# Sheet.net
KiCad netlist of a schematic drawn in Altium Designer
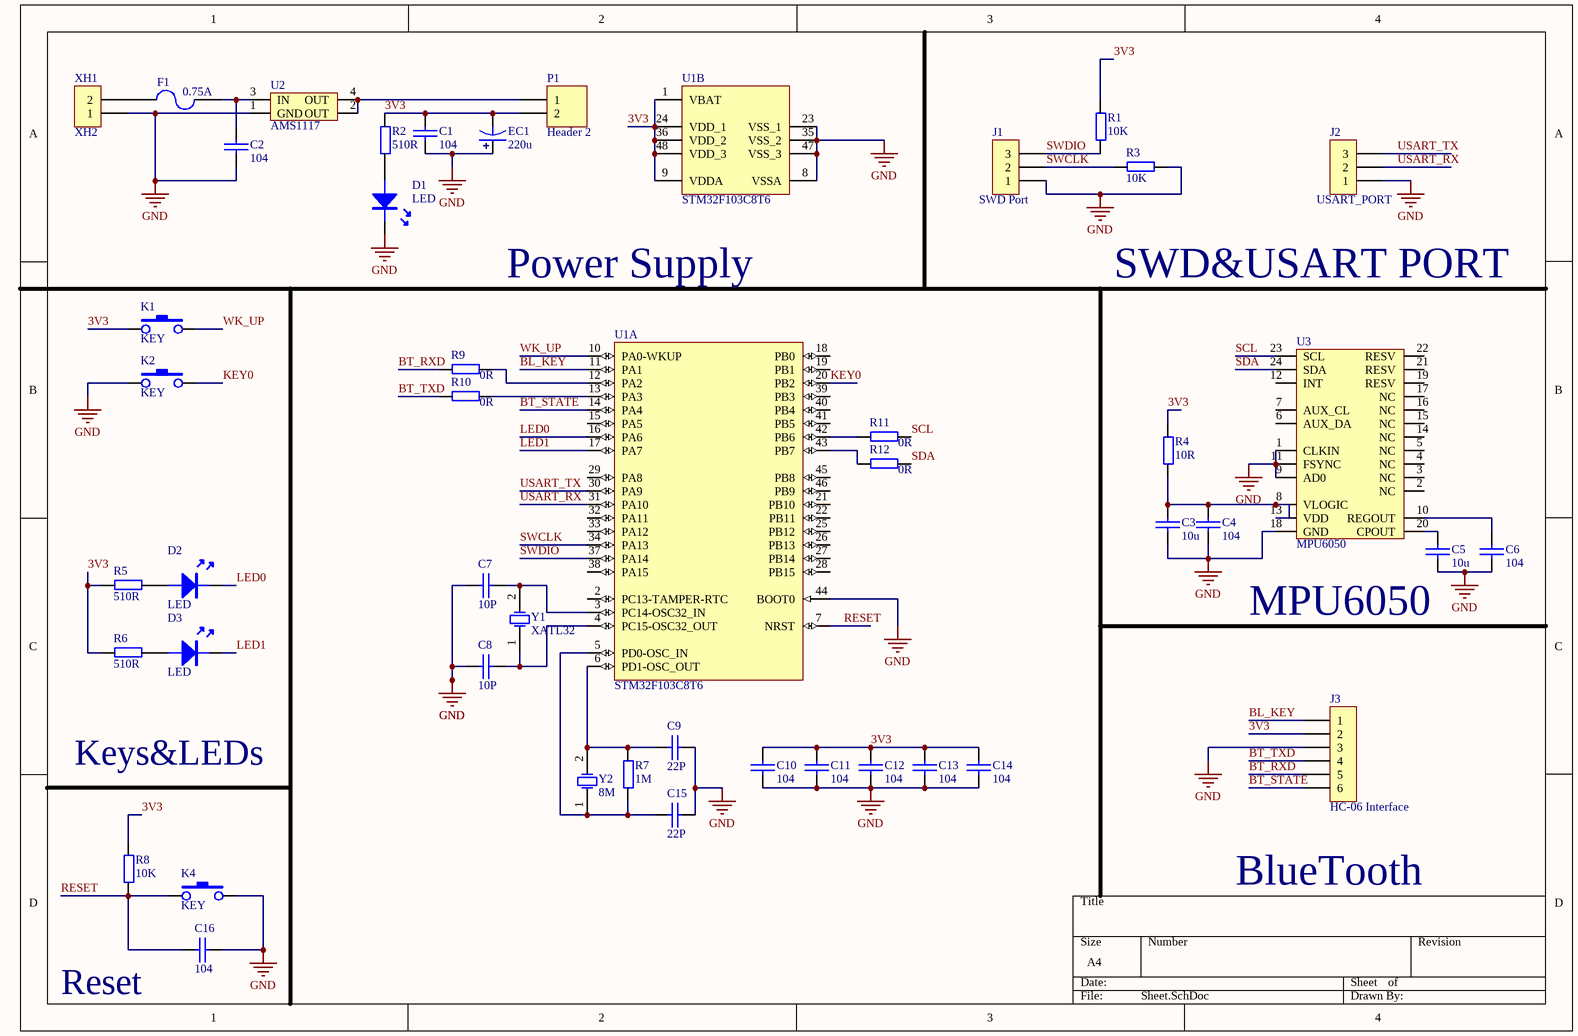
[diagram p0: Sheet.SchDoc]

(export (version "E")
  (design (tool "Eeschema 10.0.6"))
  (components
    (comp (ref "C1")
      (value "104")
      (footprint "0805C")
      (description "无极性电容")
      (libsource (lib "电容") (part "CAP"))
    )
    (comp (ref "C2")
      (value "104")
      (footprint "0805C")
      (description "无极性电容")
      (libsource (lib "电容") (part "CAP"))
    )
    (comp (ref "C3")
      (value "10u")
      (footprint "0805C")
      (description "无极性电容")
      (libsource (lib "电容") (part "CAP"))
    )
    (comp (ref "C4")
      (value "104")
      (footprint "0805C")
      (description "无极性电容")
      (libsource (lib "电容") (part "CAP"))
    )
    (comp (ref "C5")
      (value "10u")
      (footprint "0805C")
      (description "无极性电容")
      (libsource (lib "电容") (part "CAP"))
    )
    (comp (ref "C6")
      (value "104")
      (footprint "0805C")
      (description "无极性电容")
      (libsource (lib "电容") (part "CAP"))
    )
    (comp (ref "C7")
      (value "10P")
      (footprint "0805C")
      (description "无极性电容")
      (libsource (lib "电容") (part "CAP"))
    )
    (comp (ref "C8")
      (value "10P")
      (footprint "0805C")
      (description "无极性电容")
      (libsource (lib "电容") (part "CAP"))
    )
    (comp (ref "C9")
      (value "22P")
      (footprint "0805C")
      (description "无极性电容")
      (libsource (lib "电容") (part "CAP"))
    )
    (comp (ref "C10")
      (value "104")
      (footprint "0805C")
      (description "无极性电容")
      (libsource (lib "电容") (part "CAP"))
    )
    (comp (ref "C11")
      (value "104")
      (footprint "0805C")
      (description "无极性电容")
      (libsource (lib "电容") (part "CAP"))
    )
    (comp (ref "C12")
      (value "104")
      (footprint "0805C")
      (description "无极性电容")
      (libsource (lib "电容") (part "CAP"))
    )
    (comp (ref "C13")
      (value "104")
      (footprint "0805C")
      (description "无极性电容")
      (libsource (lib "电容") (part "CAP"))
    )
    (comp (ref "C14")
      (value "104")
      (footprint "0805C")
      (description "无极性电容")
      (libsource (lib "电容") (part "CAP"))
    )
    (comp (ref "C15")
      (value "22P")
      (footprint "0805C")
      (description "无极性电容")
      (libsource (lib "电容") (part "CAP"))
    )
    (comp (ref "C16")
      (value "104")
      (footprint "0805C")
      (description "无极性电容")
      (libsource (lib "电容") (part "CAP"))
    )
    (comp (ref "D1") (value "LED") (footprint "LED-0805R") (libsource (lib "LED") (part "LED")))
    (comp (ref "D2") (value "LED") (footprint "LED-0805R") (libsource (lib "LED") (part "LED")))
    (comp (ref "D3") (value "LED") (footprint "LED-0805R") (libsource (lib "LED") (part "LED")))
    (comp (ref "EC1")
      (value "220u")
      (footprint "SMD-EC5.0X5.3X5.4")
      (description "贴片电解电容")
      (libsource (lib "电容") (part "SMD_ECAP"))
    )
    (comp (ref "F1") (value "0.75A") (footprint "FUSE-1210") (libsource (lib "保险丝") (part "FUSE")))
    (comp (ref "J1")
      (value "SWD Port")
      (footprint "Pin HDR1X3/2.54mm-S")
      (libsource (lib "排针") (part "Pin HDR1X3"))
    )
    (comp (ref "J2")
      (value "USART_PORT")
      (footprint "Pin HDR1X3/2.54mm-S")
      (libsource (lib "排针") (part "Pin HDR1X3"))
    )
    (comp (ref "J3")
      (value "HC-06 Interface")
      (footprint "Fe-HDR1X6/2.54-S")
      (libsource (lib "排母") (part "Female HDR1X6"))
    )
    (comp (ref "K1") (value "KEY") (footprint "SMD-3X6X4.3") (libsource (lib "轻触开关") (part "KEY")))
    (comp (ref "K2") (value "KEY") (footprint "SMD-3X6X4.3") (libsource (lib "轻触开关") (part "KEY")))
    (comp (ref "K4") (value "KEY") (footprint "SMD-3X6X4.3") (libsource (lib "轻触开关") (part "KEY")))
    (comp (ref "P1")
      (value "Header 2")
      (footprint "HDR1X2")
      (description "Header, 2-Pin")
      (fields (field (name "PUBLISHER") "*"))
      (libsource (lib "Explorer STM32F407封装库_SCH") (part "Header 2"))
    )
    (comp (ref "R1")
      (value "10K")
      (footprint "0805")
      (libsource (lib "Explorer STM32F407封装库_SCH") (part "R"))
    )
    (comp (ref "R2")
      (value "510R")
      (footprint "0805")
      (libsource (lib "Explorer STM32F407封装库_SCH") (part "R"))
    )
    (comp (ref "R3")
      (value "10K")
      (footprint "0805")
      (libsource (lib "Explorer STM32F407封装库_SCH") (part "R"))
    )
    (comp (ref "R4")
      (value "10R")
      (footprint "0805")
      (libsource (lib "Explorer STM32F407封装库_SCH") (part "R"))
    )
    (comp (ref "R5")
      (value "510R")
      (footprint "0805")
      (libsource (lib "Explorer STM32F407封装库_SCH") (part "R"))
    )
    (comp (ref "R6")
      (value "510R")
      (footprint "0805")
      (libsource (lib "Explorer STM32F407封装库_SCH") (part "R"))
    )
    (comp (ref "R7") (value "1M") (footprint "0805") (libsource (lib "Explorer STM32F407封装库_SCH") (part "R")))
    (comp (ref "R8")
      (value "10K")
      (footprint "0805")
      (libsource (lib "Explorer STM32F407封装库_SCH") (part "R"))
    )
    (comp (ref "R9")
      (value "0R")
      (footprint "0603P")
      (libsource (lib "Explorer STM32F407封装库_SCH") (part "R"))
    )
    (comp (ref "R10")
      (value "0R")
      (footprint "0603P")
      (libsource (lib "Explorer STM32F407封装库_SCH") (part "R"))
    )
    (comp (ref "R11")
      (value "0R")
      (footprint "0603P")
      (libsource (lib "Explorer STM32F407封装库_SCH") (part "R"))
    )
    (comp (ref "R12")
      (value "0R")
      (footprint "0603P")
      (libsource (lib "Explorer STM32F407封装库_SCH") (part "R"))
    )
    (comp (ref "U1")
      (value "STM32F103C8T6")
      (footprint "STM-LQFP48_N")
      (libsource (lib "STMicroelectronics STM32 F1") (part "STM32F103C8T6"))
    )
    (comp (ref "U2")
      (value "AMS1117")
      (footprint "AMS1117")
      (libsource (lib "Explorer STM32F407封装库_SCH") (part "AMS1117"))
    )
    (comp (ref "U3")
      (value "MPU6050")
      (footprint "QFN24")
      (description "9轴运动处理传感器")
      (libsource (lib "Explorer STM32F407封装库_SCH") (part "MPU6050"))
    )
    (comp (ref "XH1") (value "XH2") (footprint "XH2/2.54mm/180") (libsource (lib "XH，VH") (part "XH2")))
    (comp (ref "Y1")
      (value "XATL32")
      (footprint "XTAL32")
      (description "Crystal Oscillator")
      (fields (field (name "PUBLISHER") "*"))
      (libsource (lib "Explorer STM32F407封装库_SCH") (part "XTAL_1"))
    )
    (comp (ref "Y2")
      (value "8M")
      (footprint "STM32_F4VE:49S_SMD")
      (description "Crystal Oscillator")
      (fields (field (name "PUBLISHER") "*"))
      (libsource (lib "Explorer STM32F407封装库_SCH") (part "XTAL"))
    )
  )
  (nets
    (net (code "1") (name "/3V3") (class "Default")
      (node (ref "C1") (pin "2") (pinfunction "2_2") (pintype "passive"))
      (node (ref "C10") (pin "2") (pinfunction "2_2") (pintype "passive"))
      (node (ref "C11") (pin "2") (pinfunction "2_2") (pintype "passive"))
      (node (ref "C12") (pin "2") (pinfunction "2_2") (pintype "passive"))
      (node (ref "C13") (pin "2") (pinfunction "2_2") (pintype "passive"))
      (node (ref "C14") (pin "2") (pinfunction "2_2") (pintype "passive"))
      (node (ref "EC1") (pin "2") (pinfunction "2_2") (pintype "passive"))
      (node (ref "J3") (pin "2") (pinfunction "2_2") (pintype "passive"))
      (node (ref "K1") (pin "1") (pinfunction "1_1") (pintype "passive"))
      (node (ref "P1") (pin "2") (pinfunction "2_2") (pintype "passive"))
      (node (ref "R1") (pin "2") (pintype "passive"))
      (node (ref "R2") (pin "2") (pintype "passive"))
      (node (ref "R4") (pin "2") (pintype "passive"))
      (node (ref "R5") (pin "2") (pintype "passive"))
      (node (ref "R6") (pin "2") (pintype "passive"))
      (node (ref "R8") (pin "2") (pintype "passive"))
      (node (ref "U1") (pin "1") (pinfunction "VBAT_1") (pintype "power_in"))
      (node (ref "U1") (pin "24") (pinfunction "VDD_1_24") (pintype "power_in"))
      (node (ref "U1") (pin "36") (pinfunction "VDD_2_36") (pintype "power_in"))
      (node (ref "U1") (pin "48") (pinfunction "VDD_3_48") (pintype "power_in"))
      (node (ref "U1") (pin "9") (pinfunction "VDDA_9") (pintype "power_in"))
    )
    (net (code "2") (name "/BL_KEY") (class "Default")
      (node (ref "J3") (pin "1") (pinfunction "1_1") (pintype "passive"))
      (node (ref "U1") (pin "11") (pinfunction "PA1_11") (pintype "bidirectional"))
    )
    (net (code "3") (name "/BT_RXD") (class "Default")
      (node (ref "J3") (pin "5") (pinfunction "5_5") (pintype "passive"))
      (node (ref "R9") (pin "2") (pintype "passive"))
    )
    (net (code "4") (name "/BT_STATE") (class "Default")
      (node (ref "J3") (pin "6") (pinfunction "6_6") (pintype "passive"))
      (node (ref "U1") (pin "14") (pinfunction "PA4_14") (pintype "bidirectional"))
    )
    (net (code "5") (name "/BT_TXD") (class "Default")
      (node (ref "J3") (pin "4") (pinfunction "4_4") (pintype "passive"))
      (node (ref "R10") (pin "2") (pintype "passive"))
    )
    (net (code "6") (name "/KEY0") (class "Default")
      (node (ref "K2") (pin "3") (pinfunction "3_3") (pintype "passive"))
      (node (ref "U1") (pin "20") (pinfunction "PB2_20") (pintype "bidirectional"))
    )
    (net (code "7") (name "/LED0") (class "Default")
      (node (ref "D2") (pin "K") (pinfunction "K_K") (pintype "passive"))
      (node (ref "U1") (pin "16") (pinfunction "PA6_16") (pintype "bidirectional"))
    )
    (net (code "8") (name "/LED1") (class "Default")
      (node (ref "D3") (pin "K") (pinfunction "K_K") (pintype "passive"))
      (node (ref "U1") (pin "17") (pinfunction "PA7_17") (pintype "bidirectional"))
    )
    (net (code "9") (name "/RESET") (class "Default")
      (node (ref "C16") (pin "2") (pinfunction "2_2") (pintype "passive"))
      (node (ref "K4") (pin "1") (pinfunction "1_1") (pintype "passive"))
      (node (ref "R8") (pin "1") (pintype "passive"))
      (node (ref "U1") (pin "7") (pinfunction "NRST_7") (pintype "bidirectional"))
    )
    (net (code "10") (name "/SCL") (class "Default")
      (node (ref "R11") (pin "1") (pintype "passive"))
      (node (ref "U3") (pin "23") (pinfunction "SCL_23") (pintype "passive"))
    )
    (net (code "11") (name "/SDA") (class "Default")
      (node (ref "R12") (pin "1") (pintype "passive"))
      (node (ref "U3") (pin "24") (pinfunction "SDA_24") (pintype "passive"))
    )
    (net (code "12") (name "/SWCLK") (class "Default")
      (node (ref "J1") (pin "2") (pinfunction "2_2") (pintype "passive"))
      (node (ref "R3") (pin "2") (pintype "passive"))
      (node (ref "U1") (pin "34") (pinfunction "PA13_34") (pintype "bidirectional"))
    )
    (net (code "13") (name "/SWDIO") (class "Default")
      (node (ref "J1") (pin "3") (pinfunction "3_3") (pintype "passive"))
      (node (ref "R1") (pin "1") (pintype "passive"))
      (node (ref "U1") (pin "37") (pinfunction "PA14_37") (pintype "bidirectional"))
    )
    (net (code "14") (name "/USART_RX") (class "Default")
      (node (ref "J2") (pin "2") (pinfunction "2_2") (pintype "passive"))
      (node (ref "U1") (pin "31") (pinfunction "PA10_31") (pintype "bidirectional"))
    )
    (net (code "15") (name "/USART_TX") (class "Default")
      (node (ref "J2") (pin "3") (pinfunction "3_3") (pintype "passive"))
      (node (ref "U1") (pin "30") (pinfunction "PA9_30") (pintype "bidirectional"))
    )
    (net (code "16") (name "/WK_UP") (class "Default")
      (node (ref "K1") (pin "3") (pinfunction "3_3") (pintype "passive"))
      (node (ref "U1") (pin "10") (pinfunction "PA0-WKUP_10") (pintype "bidirectional"))
    )
    (net (code "17") (name "GND") (class "Default")
      (node (ref "C1") (pin "1") (pinfunction "1_1") (pintype "passive"))
      (node (ref "C10") (pin "1") (pinfunction "1_1") (pintype "passive"))
      (node (ref "C11") (pin "1") (pinfunction "1_1") (pintype "passive"))
      (node (ref "C12") (pin "1") (pinfunction "1_1") (pintype "passive"))
      (node (ref "C13") (pin "1") (pinfunction "1_1") (pintype "passive"))
      (node (ref "C14") (pin "1") (pinfunction "1_1") (pintype "passive"))
      (node (ref "C15") (pin "2") (pinfunction "2_2") (pintype "passive"))
      (node (ref "C16") (pin "1") (pinfunction "1_1") (pintype "passive"))
      (node (ref "C2") (pin "1") (pinfunction "1_1") (pintype "passive"))
      (node (ref "C3") (pin "1") (pinfunction "1_1") (pintype "passive"))
      (node (ref "C4") (pin "1") (pinfunction "1_1") (pintype "passive"))
      (node (ref "C5") (pin "1") (pinfunction "1_1") (pintype "passive"))
      (node (ref "C6") (pin "1") (pinfunction "1_1") (pintype "passive"))
      (node (ref "C7") (pin "1") (pinfunction "1_1") (pintype "passive"))
      (node (ref "C8") (pin "1") (pinfunction "1_1") (pintype "passive"))
      (node (ref "C9") (pin "2") (pinfunction "2_2") (pintype "passive"))
      (node (ref "D1") (pin "K") (pinfunction "K_K") (pintype "passive"))
      (node (ref "EC1") (pin "1") (pinfunction "1_1") (pintype "passive"))
      (node (ref "J1") (pin "1") (pinfunction "1_1") (pintype "passive"))
      (node (ref "J2") (pin "1") (pinfunction "1_1") (pintype "passive"))
      (node (ref "J3") (pin "3") (pinfunction "3_3") (pintype "passive"))
      (node (ref "K2") (pin "1") (pinfunction "1_1") (pintype "passive"))
      (node (ref "K4") (pin "3") (pinfunction "3_3") (pintype "passive"))
      (node (ref "R3") (pin "1") (pintype "passive"))
      (node (ref "U1") (pin "23") (pinfunction "VSS_1_23") (pintype "power_in"))
      (node (ref "U1") (pin "35") (pinfunction "VSS_2_35") (pintype "power_in"))
      (node (ref "U1") (pin "44") (pinfunction "BOOT0_44") (pintype "input"))
      (node (ref "U1") (pin "47") (pinfunction "VSS_3_47") (pintype "power_in"))
      (node (ref "U1") (pin "8") (pinfunction "VSSA_8") (pintype "power_in"))
      (node (ref "U2") (pin "1") (pinfunction "GND_1") (pintype "passive"))
      (node (ref "U3") (pin "1") (pinfunction "CLKIN_1") (pintype "passive"))
      (node (ref "U3") (pin "11") (pinfunction "FSYNC_11") (pintype "passive"))
      (node (ref "U3") (pin "18") (pinfunction "GND_18") (pintype "passive"))
      (node (ref "U3") (pin "9") (pinfunction "AD0_9") (pintype "passive"))
      (node (ref "XH1") (pin "1") (pinfunction "1_1") (pintype "passive"))
    )
    (net (code "18") (name "Net-(D1-PadA)") (class "Default")
      (node (ref "D1") (pin "A") (pinfunction "A_A") (pintype "passive"))
      (node (ref "R2") (pin "1") (pintype "passive"))
    )
    (net (code "19") (name "Net-(D2-PadA)") (class "Default")
      (node (ref "D2") (pin "A") (pinfunction "A_A") (pintype "passive"))
      (node (ref "R5") (pin "1") (pintype "passive"))
    )
    (net (code "20") (name "Net-(D3-PadA)") (class "Default")
      (node (ref "D3") (pin "A") (pinfunction "A_A") (pintype "passive"))
      (node (ref "R6") (pin "1") (pintype "passive"))
    )
    (net (code "21") (name "Net-(F1-Pad1)") (class "Default")
      (node (ref "F1") (pin "1") (pinfunction "1_1") (pintype "passive"))
      (node (ref "XH1") (pin "2") (pinfunction "2_2") (pintype "passive"))
    )
    (net (code "22") (name "Net-(P1-Pad1)") (class "Default")
      (node (ref "P1") (pin "1") (pinfunction "1_1") (pintype "passive"))
      (node (ref "U2") (pin "2") (pinfunction "OUT_2") (pintype "passive"))
      (node (ref "U2") (pin "4") (pinfunction "OUT_4") (pintype "passive"))
    )
    (net (code "23") (name "Net-(U1A-PA2)") (class "Default")
      (node (ref "R9") (pin "1") (pintype "passive"))
      (node (ref "U1") (pin "12") (pinfunction "PA2_12") (pintype "bidirectional"))
    )
    (net (code "24") (name "Net-(U1A-PA3)") (class "Default")
      (node (ref "R10") (pin "1") (pintype "passive"))
      (node (ref "U1") (pin "13") (pinfunction "PA3_13") (pintype "bidirectional"))
    )
    (net (code "25") (name "Net-(U1A-PB6)") (class "Default")
      (node (ref "R11") (pin "2") (pintype "passive"))
      (node (ref "U1") (pin "42") (pinfunction "PB6_42") (pintype "bidirectional"))
    )
    (net (code "26") (name "Net-(U1A-PB7)") (class "Default")
      (node (ref "R12") (pin "2") (pintype "passive"))
      (node (ref "U1") (pin "43") (pinfunction "PB7_43") (pintype "bidirectional"))
    )
    (net (code "27") (name "Net-(U1A-PC14-OSC32_IN)") (class "Default")
      (node (ref "C7") (pin "2") (pinfunction "2_2") (pintype "passive"))
      (node (ref "U1") (pin "3") (pinfunction "PC14-OSC32_IN_3") (pintype "bidirectional"))
      (node (ref "Y1") (pin "2") (pinfunction "OSC2_2") (pintype "passive"))
    )
    (net (code "28") (name "Net-(U1A-PC15-OSC32_OUT)") (class "Default")
      (node (ref "C8") (pin "2") (pinfunction "2_2") (pintype "passive"))
      (node (ref "U1") (pin "4") (pinfunction "PC15-OSC32_OUT_4") (pintype "bidirectional"))
      (node (ref "Y1") (pin "1") (pinfunction "OSC1_1") (pintype "passive"))
    )
    (net (code "29") (name "Net-(U1A-PD0-OSC_IN)") (class "Default")
      (node (ref "C15") (pin "1") (pinfunction "1_1") (pintype "passive"))
      (node (ref "R7") (pin "1") (pintype "passive"))
      (node (ref "U1") (pin "5") (pinfunction "PD0-OSC_IN_5") (pintype "bidirectional"))
      (node (ref "Y2") (pin "1") (pinfunction "OSC1_1") (pintype "passive"))
    )
    (net (code "30") (name "Net-(U1A-PD1-OSC_OUT)") (class "Default")
      (node (ref "C9") (pin "1") (pinfunction "1_1") (pintype "passive"))
      (node (ref "R7") (pin "2") (pintype "passive"))
      (node (ref "U1") (pin "6") (pinfunction "PD1-OSC_OUT_6") (pintype "bidirectional"))
      (node (ref "Y2") (pin "2") (pinfunction "OSC2_2") (pintype "passive"))
    )
    (net (code "31") (name "Net-(U2-IN)") (class "Default")
      (node (ref "C2") (pin "2") (pinfunction "2_2") (pintype "passive"))
      (node (ref "F1") (pin "2") (pinfunction "2_2") (pintype "passive"))
      (node (ref "U2") (pin "3") (pinfunction "IN_3") (pintype "passive"))
    )
    (net (code "32") (name "Net-(U3-CPOUT)") (class "Default")
      (node (ref "C5") (pin "2") (pinfunction "2_2") (pintype "passive"))
      (node (ref "U3") (pin "20") (pinfunction "CPOUT_20") (pintype "passive"))
    )
    (net (code "33") (name "Net-(U3-REGOUT)") (class "Default")
      (node (ref "C6") (pin "2") (pinfunction "2_2") (pintype "passive"))
      (node (ref "U3") (pin "10") (pinfunction "REGOUT_10") (pintype "passive"))
    )
    (net (code "34") (name "Net-(U3-VDD)") (class "Default")
      (node (ref "C3") (pin "2") (pinfunction "2_2") (pintype "passive"))
      (node (ref "C4") (pin "2") (pinfunction "2_2") (pintype "passive"))
      (node (ref "R4") (pin "1") (pintype "passive"))
      (node (ref "U3") (pin "13") (pinfunction "VDD_13") (pintype "passive"))
      (node (ref "U3") (pin "8") (pinfunction "VLOGIC_8") (pintype "passive"))
    )
    (net (code "35") (name "unconnected-(U1A-PA5-Pad15)") (class "Default")
      (node (ref "U1") (pin "15") (pinfunction "PA5_15") (pintype "bidirectional"))
    )
    (net (code "36") (name "unconnected-(U1A-PA8-Pad29)") (class "Default")
      (node (ref "U1") (pin "29") (pinfunction "PA8_29") (pintype "bidirectional"))
    )
    (net (code "37") (name "unconnected-(U1A-PA11-Pad32)") (class "Default")
      (node (ref "U1") (pin "32") (pinfunction "PA11_32") (pintype "bidirectional"))
    )
    (net (code "38") (name "unconnected-(U1A-PA12-Pad33)") (class "Default")
      (node (ref "U1") (pin "33") (pinfunction "PA12_33") (pintype "bidirectional"))
    )
    (net (code "39") (name "unconnected-(U1A-PA15-Pad38)") (class "Default")
      (node (ref "U1") (pin "38") (pinfunction "PA15_38") (pintype "bidirectional"))
    )
    (net (code "40") (name "unconnected-(U1A-PB0-Pad18)") (class "Default")
      (node (ref "U1") (pin "18") (pinfunction "PB0_18") (pintype "bidirectional"))
    )
    (net (code "41") (name "unconnected-(U1A-PB1-Pad19)") (class "Default")
      (node (ref "U1") (pin "19") (pinfunction "PB1_19") (pintype "bidirectional"))
    )
    (net (code "42") (name "unconnected-(U1A-PB3-Pad39)") (class "Default")
      (node (ref "U1") (pin "39") (pinfunction "PB3_39") (pintype "bidirectional"))
    )
    (net (code "43") (name "unconnected-(U1A-PB4-Pad40)") (class "Default")
      (node (ref "U1") (pin "40") (pinfunction "PB4_40") (pintype "bidirectional"))
    )
    (net (code "44") (name "unconnected-(U1A-PB5-Pad41)") (class "Default")
      (node (ref "U1") (pin "41") (pinfunction "PB5_41") (pintype "bidirectional"))
    )
    (net (code "45") (name "unconnected-(U1A-PB8-Pad45)") (class "Default")
      (node (ref "U1") (pin "45") (pinfunction "PB8_45") (pintype "bidirectional"))
    )
    (net (code "46") (name "unconnected-(U1A-PB9-Pad46)") (class "Default")
      (node (ref "U1") (pin "46") (pinfunction "PB9_46") (pintype "bidirectional"))
    )
    (net (code "47") (name "unconnected-(U1A-PB10-Pad21)") (class "Default")
      (node (ref "U1") (pin "21") (pinfunction "PB10_21") (pintype "bidirectional"))
    )
    (net (code "48") (name "unconnected-(U1A-PB11-Pad22)") (class "Default")
      (node (ref "U1") (pin "22") (pinfunction "PB11_22") (pintype "bidirectional"))
    )
    (net (code "49") (name "unconnected-(U1A-PB12-Pad25)") (class "Default")
      (node (ref "U1") (pin "25") (pinfunction "PB12_25") (pintype "bidirectional"))
    )
    (net (code "50") (name "unconnected-(U1A-PB13-Pad26)") (class "Default")
      (node (ref "U1") (pin "26") (pinfunction "PB13_26") (pintype "bidirectional"))
    )
    (net (code "51") (name "unconnected-(U1A-PB14-Pad27)") (class "Default")
      (node (ref "U1") (pin "27") (pinfunction "PB14_27") (pintype "bidirectional"))
    )
    (net (code "52") (name "unconnected-(U1A-PB15-Pad28)") (class "Default")
      (node (ref "U1") (pin "28") (pinfunction "PB15_28") (pintype "bidirectional"))
    )
    (net (code "53") (name "unconnected-(U1A-PC13-TAMPER-RTC-Pad2)") (class "Default")
      (node (ref "U1") (pin "2") (pinfunction "PC13-TAMPER-RTC_2") (pintype "bidirectional"))
    )
    (net (code "54") (name "unconnected-(U3-AUX_CL-Pad7)") (class "Default")
      (node (ref "U3") (pin "7") (pinfunction "AUX_CL_7") (pintype "passive"))
    )
    (net (code "55") (name "unconnected-(U3-AUX_DA-Pad6)") (class "Default")
      (node (ref "U3") (pin "6") (pinfunction "AUX_DA_6") (pintype "passive"))
    )
    (net (code "56") (name "unconnected-(U3-INT-Pad12)") (class "Default")
      (node (ref "U3") (pin "12") (pinfunction "INT_12") (pintype "passive"))
    )
    (net (code "57") (name "unconnected-(U3-NC-Pad2)") (class "Default")
      (node (ref "U3") (pin "2") (pinfunction "NC_2") (pintype "passive"))
    )
    (net (code "58") (name "unconnected-(U3-NC-Pad3)") (class "Default")
      (node (ref "U3") (pin "3") (pinfunction "NC_3") (pintype "passive"))
    )
    (net (code "59") (name "unconnected-(U3-NC-Pad4)") (class "Default")
      (node (ref "U3") (pin "4") (pinfunction "NC_4") (pintype "passive"))
    )
    (net (code "60") (name "unconnected-(U3-NC-Pad5)") (class "Default")
      (node (ref "U3") (pin "5") (pinfunction "NC_5") (pintype "passive"))
    )
    (net (code "61") (name "unconnected-(U3-NC-Pad14)") (class "Default")
      (node (ref "U3") (pin "14") (pinfunction "NC_14") (pintype "passive"))
    )
    (net (code "62") (name "unconnected-(U3-NC-Pad15)") (class "Default")
      (node (ref "U3") (pin "15") (pinfunction "NC_15") (pintype "passive"))
    )
    (net (code "63") (name "unconnected-(U3-NC-Pad16)") (class "Default")
      (node (ref "U3") (pin "16") (pinfunction "NC_16") (pintype "passive"))
    )
    (net (code "64") (name "unconnected-(U3-NC-Pad17)") (class "Default")
      (node (ref "U3") (pin "17") (pinfunction "NC_17") (pintype "passive"))
    )
    (net (code "65") (name "unconnected-(U3-RESV-Pad19)") (class "Default")
      (node (ref "U3") (pin "19") (pinfunction "RESV_19") (pintype "passive"))
    )
    (net (code "66") (name "unconnected-(U3-RESV-Pad21)") (class "Default")
      (node (ref "U3") (pin "21") (pinfunction "RESV_21") (pintype "passive"))
    )
    (net (code "67") (name "unconnected-(U3-RESV-Pad22)") (class "Default")
      (node (ref "U3") (pin "22") (pinfunction "RESV_22") (pintype "passive"))
    )
  )
)
